# ESP_SCH.net
KiCad netlist of a schematic drawn in Altium Designer
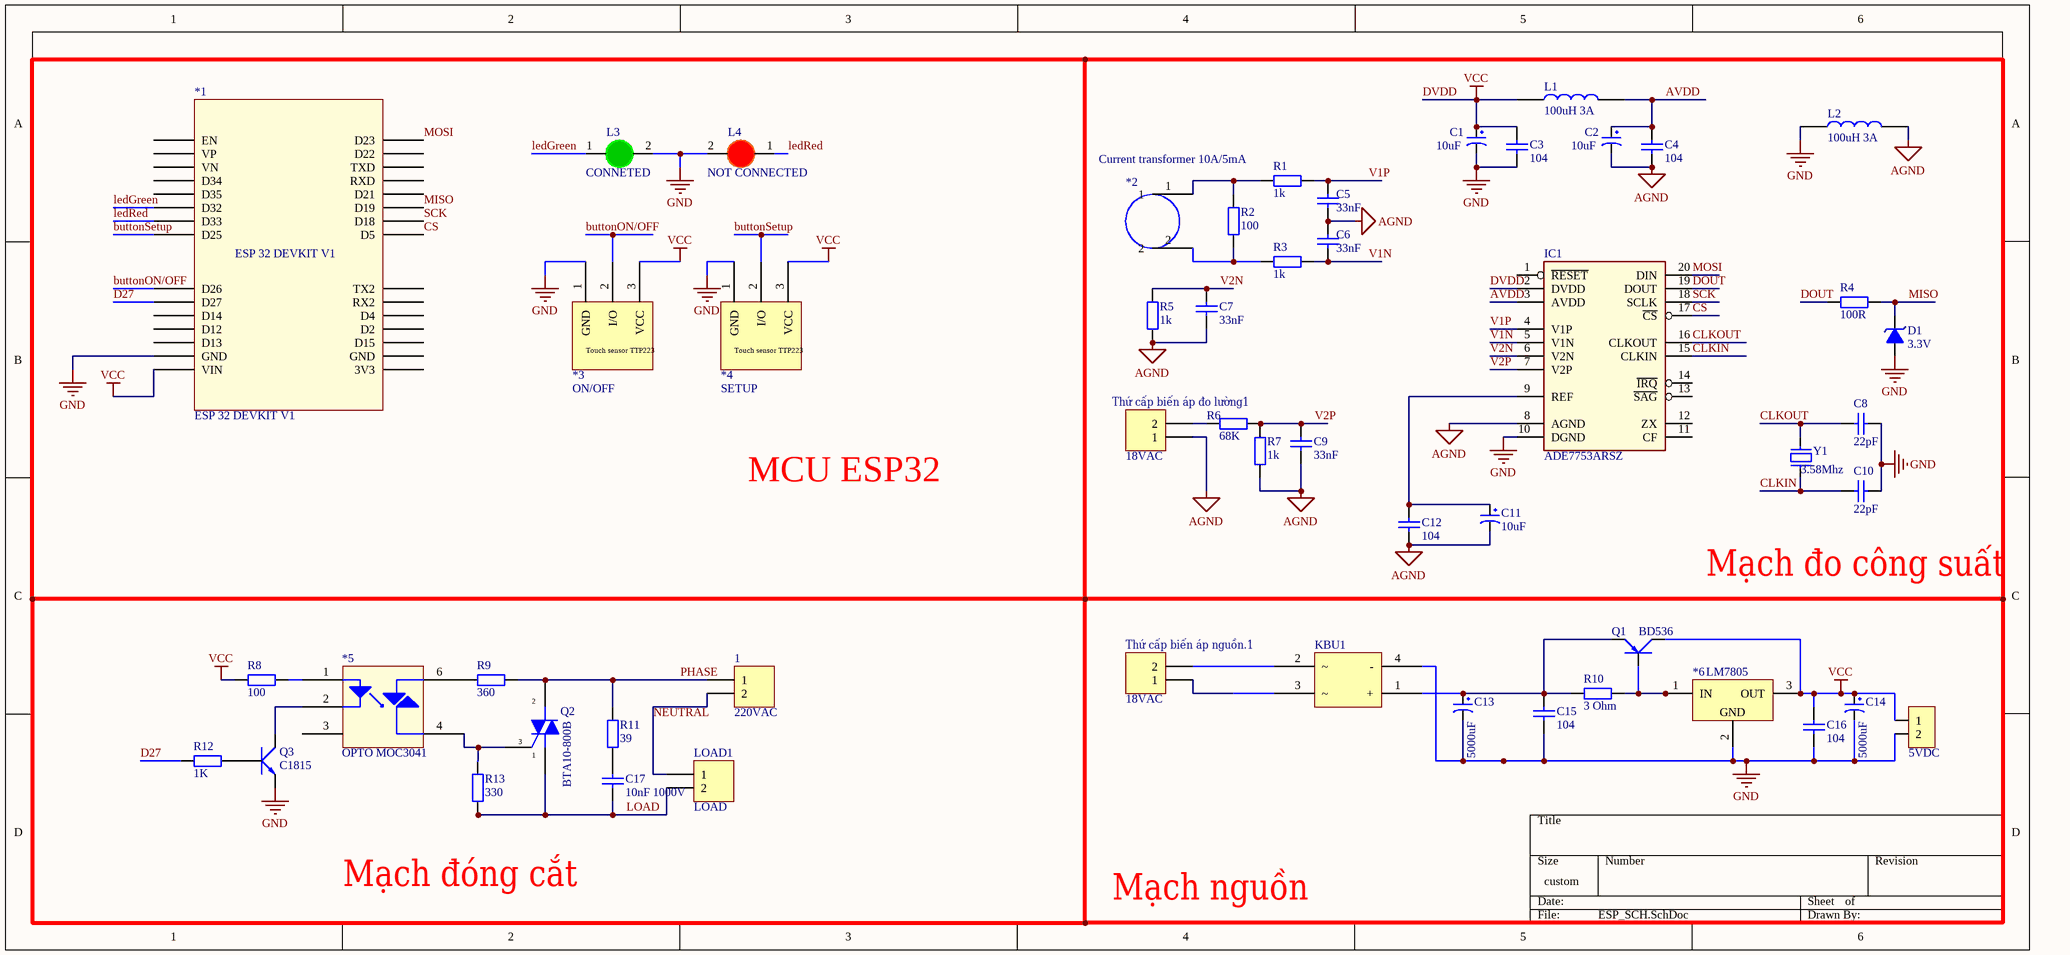
[diagram p0: ESP_SCH.SchDoc]

(export (version "E")
  (design (tool "Eeschema 10.0.6"))
  (components
    (comp (ref "*1")
      (value "ESP 32 DEVKIT V1")
      (footprint "ESP32 DEVKIT V1")
      (libsource (lib "TrungVan_Lib") (part "ESP 32 DEVKIT V1"))
    )
    (comp (ref "*2")
      (value "Current transformer 10A/5mA")
      (footprint "5A/5mA")
      (description "Current transformer 5A/5mA")
      (libsource (lib "TrungVan_Lib") (part "Current transformer"))
    )
    (comp (ref "*3")
      (value "ON/OFF")
      (footprint "TTP223")
      (libsource (lib "TrungVan_Lib") (part "Touch sensor"))
    )
    (comp (ref "*4")
      (value "SETUP")
      (footprint "TTP223")
      (libsource (lib "TrungVan_Lib") (part "Touch sensor"))
    )
    (comp (ref "*5")
      (value "OPTO MOC3041")
      (footprint "MOC3021")
      (libsource (lib "TrungVan_Lib") (part "OPTO MOC3021"))
    )
    (comp (ref "*6") (value "LM7805") (footprint "TO220") (libsource (lib "TrungVan_Lib") (part "LM780x")))
    (comp (ref "1")
      (value "220VAC")
      (footprint "KF127_2P")
      (description "Header, 2-Pin, pitch 5.08mm")
      (fields (field (name "MPN") "KF127-2P"))
      (libsource (lib "BYTECH_HW_LIB_2019 (1)") (part "KF127 2P"))
    )
    (comp (ref "C1")
      (value "10uF")
      (footprint "tu hoa 4mm")
      (description "Cắm")
      (libsource (lib "TrungVan_Lib") (part "Tu Hoa 10uF 25V 4x7"))
    )
    (comp (ref "C2")
      (value "10uF")
      (footprint "tu hoa 4mm")
      (description "Cắm")
      (libsource (lib "TrungVan_Lib") (part "Tu Hoa 10uF 25V 4x7"))
    )
    (comp (ref "C3")
      (value "104")
      (footprint "tu gom")
      (description "Cắm")
      (libsource (lib "TrungVan_Lib") (part "Tu gom 104 50V"))
    )
    (comp (ref "C4")
      (value "104")
      (footprint "tu gom")
      (description "Cắm")
      (libsource (lib "TrungVan_Lib") (part "Tu gom 104 50V"))
    )
    (comp (ref "C5")
      (value "33nF")
      (footprint "tu gom")
      (description "Cắm")
      (libsource (lib "TrungVan_Lib") (part "Tu gom 333 50V"))
    )
    (comp (ref "C6")
      (value "33nF")
      (footprint "tu gom")
      (description "Cắm")
      (libsource (lib "TrungVan_Lib") (part "Tu gom 333 50V"))
    )
    (comp (ref "C7")
      (value "33nF")
      (footprint "tu gom")
      (description "Cắm")
      (libsource (lib "TrungVan_Lib") (part "Tu gom 333 50V"))
    )
    (comp (ref "C8")
      (value "22pF")
      (footprint "tu gom")
      (description "Cắm")
      (libsource (lib "TrungVan_Lib") (part "Tu gom 221 50V"))
    )
    (comp (ref "C9")
      (value "33nF")
      (footprint "tu gom")
      (description "Cắm")
      (libsource (lib "TrungVan_Lib") (part "Tu gom 333 50V"))
    )
    (comp (ref "C10")
      (value "22pF")
      (footprint "tu gom")
      (description "Cắm")
      (libsource (lib "TrungVan_Lib") (part "Tu gom 221 50V"))
    )
    (comp (ref "C11")
      (value "10uF")
      (footprint "tu hoa 4mm")
      (description "Cắm")
      (libsource (lib "TrungVan_Lib") (part "Tu Hoa 10uF 25V 4x7"))
    )
    (comp (ref "C12")
      (value "104")
      (footprint "tu gom")
      (description "Cắm")
      (libsource (lib "TrungVan_Lib") (part "Tu gom 104 50V"))
    )
    (comp (ref "C13")
      (value "5000uF")
      (footprint "tu hoa 8mm")
      (description "Cắm")
      (libsource (lib "TrungVan_Lib") (part "Tu Hoa 1000uF 16V 8x20"))
    )
    (comp (ref "C14")
      (value "5000uF")
      (footprint "tu hoa 8mm")
      (description "Cắm")
      (libsource (lib "TrungVan_Lib") (part "Tu Hoa 1000uF 16V 8x20"))
    )
    (comp (ref "C15")
      (value "104")
      (footprint "tu gom")
      (description "Cắm")
      (libsource (lib "TrungVan_Lib") (part "Tu gom 473 50V"))
    )
    (comp (ref "C16")
      (value "104")
      (footprint "tu gom")
      (description "Cắm")
      (libsource (lib "TrungVan_Lib") (part "Tu gom 473 50V"))
    )
    (comp (ref "C17")
      (value "10nF 1000V")
      (footprint "tu tantalum dip5.08")
      (description "Cắm")
      (libsource (lib "TrungVan_Lib") (part "Tu tantalum 10nF DIP5.08"))
    )
    (comp (ref "D1")
      (value "3.3V")
      (footprint "DIODE 0.5A")
      (description "Dán")
      (libsource (lib "TrungVan_Lib") (part "Diode Zener 3.3V"))
    )
    (comp (ref "IC1")
      (value "ADE7753ARSZ")
      (footprint "ADE7753 dip")
      (description "Dán")
      (libsource (lib "TrungVan_Lib") (part "ADE7753 SMD SOP20"))
    )
    (comp (ref "JP1")
      (value "5VDC")
      (footprint "JP 1x2 DT")
      (description "Cắm")
      (libsource (lib "TrungVan_Lib") (part "JP 1x2 2.54 Duc Thang"))
    )
    (comp (ref "KBU1")
      (value "10A 1000V")
      (footprint "DIODE CAU 10A CAM")
      (description "Cắm")
      (libsource (lib "TrungVan_Lib") (part "Diode CAU 10A"))
    )
    (comp (ref "L1")
      (value "100uH 3A")
      (footprint "CUON_CAM 100UH")
      (description "Dán")
      (libsource (lib "TrungVan_Lib") (part "CUON CAM 100uH DIP"))
    )
    (comp (ref "L2")
      (value "100uH 3A")
      (footprint "CUON_CAM 100UH")
      (description "Dán")
      (libsource (lib "TrungVan_Lib") (part "CUON CAM 100uH DIP"))
    )
    (comp (ref "L3")
      (value "CONNETED")
      (footprint "LED-3MM-GREEN")
      (description "Cắm")
      (libsource (lib "TrungVan_Lib") (part "LED 3mm Xanh La"))
    )
    (comp (ref "L4")
      (value "NOT CONNECTED")
      (footprint "LED-3MM-RED")
      (description "Cắm")
      (libsource (lib "TrungVan_Lib") (part "LED 3mm Do"))
    )
    (comp (ref "LOAD1")
      (value "LOAD")
      (footprint "KF127_2P")
      (description "Header, 2-Pin, pitch 5.08mm")
      (fields (field (name "MPN") "KF127-2P"))
      (libsource (lib "BYTECH_HW_LIB_2019 (1)") (part "KF127 2P"))
    )
    (comp (ref "Q1")
      (value "BD536")
      (footprint "to220")
      (description "PNP 600mW, ECB")
      (libsource (lib "TrungVan_Lib") (part "A1015"))
    )
    (comp (ref "Q2")
      (value "BTA10-800B")
      (footprint "to220")
      (description "TRIAC 600V 40A TOP3")
      (fields
        (field (name "MANUFACTURER") "STMicroelectronics")
        (field (name "MANUFACTURER PART NUMBER") "BTA41-600BRG")
      )
      (libsource (lib "BYTECH_HW_LIB_2019 (1)") (part "BTA41-600BRG"))
    )
    (comp (ref "Q3")
      (value "C1815")
      (footprint "TO92")
      (description "NPN transistor")
      (libsource (lib "TrungVan_Lib") (part "C1815"))
    )
    (comp (ref "R1")
      (value "1k")
      (footprint "Dien tro")
      (description "Cắm")
      (libsource (lib "TrungVan_Lib") (part "Resistor"))
    )
    (comp (ref "R2")
      (value "100")
      (footprint "Dien tro")
      (description "Cắm")
      (libsource (lib "TrungVan_Lib") (part "Resistor"))
    )
    (comp (ref "R3")
      (value "1k")
      (footprint "Dien tro")
      (description "Cắm")
      (libsource (lib "TrungVan_Lib") (part "Resistor"))
    )
    (comp (ref "R4")
      (value "100R")
      (footprint "Dien tro")
      (description "Cắm")
      (libsource (lib "TrungVan_Lib") (part "Resistor"))
    )
    (comp (ref "R5")
      (value "1k")
      (footprint "Dien tro")
      (description "Cắm")
      (libsource (lib "TrungVan_Lib") (part "Resistor"))
    )
    (comp (ref "R6")
      (value "68K")
      (footprint "Dien tro")
      (description "Cắm")
      (libsource (lib "TrungVan_Lib") (part "Resistor"))
    )
    (comp (ref "R7")
      (value "1k")
      (footprint "Dien tro")
      (description "Cắm")
      (libsource (lib "TrungVan_Lib") (part "Resistor"))
    )
    (comp (ref "R8")
      (value "100")
      (footprint "Dien tro")
      (description "Cắm")
      (libsource (lib "TrungVan_Lib") (part "Resistor"))
    )
    (comp (ref "R9")
      (value "360")
      (footprint "Dien tro")
      (description "Cắm")
      (libsource (lib "TrungVan_Lib") (part "Resistor"))
    )
    (comp (ref "R10")
      (value "3 Ohm")
      (footprint "Dien tro")
      (description "Cắm")
      (libsource (lib "TrungVan_Lib") (part "Resistor"))
    )
    (comp (ref "R11")
      (value "39")
      (footprint "Dien tro")
      (description "Cắm")
      (libsource (lib "TrungVan_Lib") (part "Resistor"))
    )
    (comp (ref "R12")
      (value "1K")
      (footprint "Dien tro")
      (description "Cắm")
      (libsource (lib "TrungVan_Lib") (part "Resistor"))
    )
    (comp (ref "R13")
      (value "330")
      (footprint "Dien tro")
      (description "Cắm")
      (libsource (lib "TrungVan_Lib") (part "Resistor"))
    )
    (comp (ref "Thứ cấp biến áp nguồn.1")
      (value "18VAC")
      (footprint "KF127_2P")
      (description "Header, 2-Pin, pitch 5.08mm")
      (fields (field (name "MPN") "KF127-2P"))
      (libsource (lib "") (part "KF127 2P_1"))
    )
    (comp (ref "Thứ cấp biến áp đo lường1")
      (value "18VAC")
      (footprint "KF127_2P")
      (description "Header, 2-Pin, pitch 5.08mm")
      (fields (field (name "MPN") "KF127-2P"))
      (libsource (lib "") (part "KF127 2P_1"))
    )
    (comp (ref "Y1")
      (value "3.58Mhz")
      (footprint "Thach Anh 2 chan cam")
      (description "Crystal For all Crystal 2pin.")
      (libsource (lib "TrungVan_Lib") (part "Thach Anh 2 chan Cam"))
    )
  )
  (nets
    (net (code "1") (name "/AVDD") (class "Default")
      (node (ref "C2") (pin "1") (pinfunction "1_1") (pintype "passive"))
      (node (ref "C4") (pin "1") (pinfunction "1_1") (pintype "passive"))
      (node (ref "IC1") (pin "3") (pinfunction "AVDD_3") (pintype "passive"))
      (node (ref "L1") (pin "2") (pinfunction "2_2") (pintype "passive"))
    )
    (net (code "2") (name "/CLKIN") (class "Default")
      (node (ref "C10") (pin "2") (pinfunction "2_2") (pintype "passive"))
      (node (ref "IC1") (pin "15") (pinfunction "CLKIN_15") (pintype "passive"))
      (node (ref "Y1") (pin "1") (pinfunction "1_1") (pintype "passive"))
    )
    (net (code "3") (name "/CLKOUT") (class "Default")
      (node (ref "C8") (pin "2") (pinfunction "2_2") (pintype "passive"))
      (node (ref "IC1") (pin "16") (pinfunction "CLKOUT_16") (pintype "passive"))
      (node (ref "Y1") (pin "2") (pinfunction "2_2") (pintype "passive"))
    )
    (net (code "4") (name "/CS") (class "Default")
      (node (ref "*1") (pin "23") (pinfunction "D5_23") (pintype "passive"))
      (node (ref "IC1") (pin "17") (pinfunction "~{CS}_17") (pintype "passive"))
    )
    (net (code "5") (name "/D27") (class "Default")
      (node (ref "*1") (pin "10") (pinfunction "D27_10") (pintype "passive"))
      (node (ref "R12") (pin "2") (pinfunction "2_2") (pintype "passive"))
    )
    (net (code "6") (name "/DOUT") (class "Default")
      (node (ref "IC1") (pin "19") (pinfunction "DOUT_19") (pintype "passive"))
      (node (ref "R4") (pin "2") (pinfunction "2_2") (pintype "passive"))
    )
    (net (code "7") (name "/LOAD") (class "Default")
      (node (ref "C17") (pin "2") (pinfunction "2_2") (pintype "passive"))
      (node (ref "LOAD1") (pin "2") (pinfunction "2_2") (pintype "passive"))
      (node (ref "Q2") (pin "1") (pinfunction "M1_1") (pintype "passive"))
      (node (ref "R13") (pin "1") (pinfunction "1_1") (pintype "passive"))
    )
    (net (code "8") (name "/MISO") (class "Default")
      (node (ref "*1") (pin "25") (pinfunction "D19_25") (pintype "passive"))
      (node (ref "D1") (pin "2") (pinfunction "K_2") (pintype "passive"))
      (node (ref "R4") (pin "1") (pinfunction "1_1") (pintype "passive"))
    )
    (net (code "9") (name "/MOSI") (class "Default")
      (node (ref "*1") (pin "30") (pinfunction "D23_30") (pintype "passive"))
      (node (ref "IC1") (pin "20") (pinfunction "DIN_20") (pintype "passive"))
    )
    (net (code "10") (name "/NEUTRAL") (class "Default")
      (node (ref "1") (pin "2") (pinfunction "2_2") (pintype "passive"))
      (node (ref "LOAD1") (pin "1") (pinfunction "1_1") (pintype "passive"))
    )
    (net (code "11") (name "/PHASE") (class "Default")
      (node (ref "1") (pin "1") (pinfunction "1_1") (pintype "passive"))
      (node (ref "Q2") (pin "2") (pinfunction "M2_2") (pintype "passive"))
      (node (ref "R11") (pin "2") (pinfunction "2_2") (pintype "passive"))
      (node (ref "R9") (pin "2") (pinfunction "2_2") (pintype "passive"))
    )
    (net (code "12") (name "/SCK") (class "Default")
      (node (ref "*1") (pin "24") (pinfunction "D18_24") (pintype "passive"))
      (node (ref "IC1") (pin "18") (pinfunction "SCLK_18") (pintype "passive"))
    )
    (net (code "13") (name "/V1N") (class "Default")
      (node (ref "C6") (pin "2") (pinfunction "2_2") (pintype "passive"))
      (node (ref "IC1") (pin "5") (pinfunction "V1N_5") (pintype "passive"))
      (node (ref "R3") (pin "1") (pinfunction "1_1") (pintype "passive"))
    )
    (net (code "14") (name "/V1P") (class "Default")
      (node (ref "C5") (pin "1") (pinfunction "1_1") (pintype "passive"))
      (node (ref "IC1") (pin "4") (pinfunction "V1P_4") (pintype "passive"))
      (node (ref "R1") (pin "1") (pinfunction "1_1") (pintype "passive"))
    )
    (net (code "15") (name "/V2N") (class "Default")
      (node (ref "C7") (pin "1") (pinfunction "1_1") (pintype "passive"))
      (node (ref "IC1") (pin "6") (pinfunction "V2N_6") (pintype "passive"))
      (node (ref "R5") (pin "2") (pinfunction "2_2") (pintype "passive"))
    )
    (net (code "16") (name "/V2P") (class "Default")
      (node (ref "C9") (pin "1") (pinfunction "1_1") (pintype "passive"))
      (node (ref "IC1") (pin "7") (pinfunction "V2P_7") (pintype "passive"))
      (node (ref "R6") (pin "1") (pinfunction "1_1") (pintype "passive"))
      (node (ref "R7") (pin "2") (pinfunction "2_2") (pintype "passive"))
    )
    (net (code "17") (name "/buttonON{slash}OFF") (class "Default")
      (node (ref "*1") (pin "9") (pinfunction "D26_9") (pintype "passive"))
      (node (ref "*3") (pin "2") (pinfunction "I/O_2") (pintype "passive"))
    )
    (net (code "18") (name "/buttonSetup") (class "Default")
      (node (ref "*1") (pin "8") (pinfunction "D25_8") (pintype "passive"))
      (node (ref "*4") (pin "2") (pinfunction "I/O_2") (pintype "passive"))
    )
    (net (code "19") (name "/ledGreen") (class "Default")
      (node (ref "*1") (pin "6") (pinfunction "D32_6") (pintype "passive"))
      (node (ref "L3") (pin "1") (pinfunction "A_1") (pintype "passive"))
    )
    (net (code "20") (name "/ledRed") (class "Default")
      (node (ref "*1") (pin "7") (pinfunction "D33_7") (pintype "passive"))
      (node (ref "L4") (pin "1") (pinfunction "A_1") (pintype "passive"))
    )
    (net (code "21") (name "AGND") (class "Default")
      (node (ref "C11") (pin "2") (pinfunction "2_2") (pintype "passive"))
      (node (ref "C12") (pin "2") (pinfunction "2_2") (pintype "passive"))
      (node (ref "C2") (pin "2") (pinfunction "2_2") (pintype "passive"))
      (node (ref "C4") (pin "2") (pinfunction "2_2") (pintype "passive"))
      (node (ref "C5") (pin "2") (pinfunction "2_2") (pintype "passive"))
      (node (ref "C6") (pin "1") (pinfunction "1_1") (pintype "passive"))
      (node (ref "C7") (pin "2") (pinfunction "2_2") (pintype "passive"))
      (node (ref "C9") (pin "2") (pinfunction "2_2") (pintype "passive"))
      (node (ref "IC1") (pin "8") (pinfunction "AGND_8") (pintype "passive"))
      (node (ref "L2") (pin "2") (pinfunction "2_2") (pintype "passive"))
      (node (ref "R5") (pin "1") (pinfunction "1_1") (pintype "passive"))
      (node (ref "R7") (pin "1") (pinfunction "1_1") (pintype "passive"))
      (node (ref "Thứ cấp biến áp đo lường1") (pin "1") (pinfunction "1_1") (pintype "passive"))
    )
    (net (code "22") (name "GND") (class "Default")
      (node (ref "*1") (pin "14") (pinfunction "GND_14") (pintype "passive"))
      (node (ref "*3") (pin "1") (pinfunction "GND_1") (pintype "passive"))
      (node (ref "*4") (pin "1") (pinfunction "GND_1") (pintype "passive"))
      (node (ref "*6") (pin "2") (pinfunction "GND_2") (pintype "power_in"))
      (node (ref "C1") (pin "2") (pinfunction "2_2") (pintype "passive"))
      (node (ref "C10") (pin "1") (pinfunction "1_1") (pintype "passive"))
      (node (ref "C13") (pin "2") (pinfunction "2_2") (pintype "passive"))
      (node (ref "C14") (pin "2") (pinfunction "2_2") (pintype "passive"))
      (node (ref "C15") (pin "2") (pinfunction "2_2") (pintype "passive"))
      (node (ref "C16") (pin "2") (pinfunction "2_2") (pintype "passive"))
      (node (ref "C3") (pin "2") (pinfunction "2_2") (pintype "passive"))
      (node (ref "C8") (pin "1") (pinfunction "1_1") (pintype "passive"))
      (node (ref "D1") (pin "1") (pinfunction "A_1") (pintype "passive"))
      (node (ref "IC1") (pin "10") (pinfunction "DGND_10") (pintype "passive"))
      (node (ref "JP1") (pin "2") (pinfunction "2_2") (pintype "passive"))
      (node (ref "KBU1") (pin "4") (pinfunction "-_4") (pintype "passive"))
      (node (ref "L2") (pin "1") (pinfunction "1_1") (pintype "passive"))
      (node (ref "L3") (pin "2") (pinfunction "K_2") (pintype "passive"))
      (node (ref "L4") (pin "2") (pinfunction "K_2") (pintype "passive"))
      (node (ref "Q3") (pin "1") (pinfunction "E_1") (pintype "passive"))
    )
    (net (code "23") (name "Net-(*2-Pad1)") (class "Default")
      (node (ref "*2") (pin "1") (pinfunction "1_1") (pintype "passive"))
      (node (ref "R1") (pin "2") (pinfunction "2_2") (pintype "passive"))
      (node (ref "R2") (pin "2") (pinfunction "2_2") (pintype "passive"))
    )
    (net (code "24") (name "Net-(*2-Pad2)") (class "Default")
      (node (ref "*2") (pin "2") (pinfunction "2_2") (pintype "passive"))
      (node (ref "R2") (pin "1") (pinfunction "1_1") (pintype "passive"))
      (node (ref "R3") (pin "2") (pinfunction "2_2") (pintype "passive"))
    )
    (net (code "25") (name "Net-(*5-0)") (class "Default")
      (node (ref "*5") (pin "6") (pinfunction "0_6") (pintype "passive"))
      (node (ref "R9") (pin "1") (pinfunction "1_1") (pintype "passive"))
    )
    (net (code "26") (name "Net-(*5-2)") (class "Default")
      (node (ref "*5") (pin "4") (pinfunction "2_4") (pintype "passive"))
      (node (ref "Q2") (pin "3") (pinfunction "G_3") (pintype "passive"))
      (node (ref "R13") (pin "2") (pinfunction "2_2") (pintype "passive"))
    )
    (net (code "27") (name "Net-(*5-3)") (class "Default")
      (node (ref "*5") (pin "1") (pinfunction "3_1") (pintype "passive"))
      (node (ref "R8") (pin "1") (pinfunction "1_1") (pintype "passive"))
    )
    (net (code "28") (name "Net-(*5-4)") (class "Default")
      (node (ref "*5") (pin "2") (pinfunction "4_2") (pintype "passive"))
      (node (ref "Q3") (pin "2") (pinfunction "C_2") (pintype "passive"))
    )
    (net (code "29") (name "Net-(*6-IN)") (class "Default")
      (node (ref "*6") (pin "1") (pinfunction "IN_1") (pintype "power_in"))
      (node (ref "Q1") (pin "3") (pinfunction "B_3") (pintype "passive"))
      (node (ref "R10") (pin "1") (pinfunction "1_1") (pintype "passive"))
    )
    (net (code "30") (name "Net-(C17-Pad1)") (class "Default")
      (node (ref "C17") (pin "1") (pinfunction "1_1") (pintype "passive"))
      (node (ref "R11") (pin "1") (pinfunction "1_1") (pintype "passive"))
    )
    (net (code "31") (name "Net-(IC1-REF)") (class "Default")
      (node (ref "C11") (pin "1") (pinfunction "1_1") (pintype "passive"))
      (node (ref "C12") (pin "1") (pinfunction "1_1") (pintype "passive"))
      (node (ref "IC1") (pin "9") (pinfunction "REF_9") (pintype "passive"))
    )
    (net (code "32") (name "Net-(KBU1-+)") (class "Default")
      (node (ref "C13") (pin "1") (pinfunction "1_1") (pintype "passive"))
      (node (ref "C15") (pin "1") (pinfunction "1_1") (pintype "passive"))
      (node (ref "KBU1") (pin "1") (pinfunction "+_1") (pintype "passive"))
      (node (ref "Q1") (pin "1") (pinfunction "E_1") (pintype "passive"))
      (node (ref "R10") (pin "2") (pinfunction "2_2") (pintype "passive"))
    )
    (net (code "33") (name "Net-(KBU1-~-Pad2)") (class "Default")
      (node (ref "KBU1") (pin "2") (pinfunction "~_2") (pintype "passive"))
      (node (ref "Thứ cấp biến áp nguồn.1") (pin "2") (pinfunction "2_2") (pintype "passive"))
    )
    (net (code "34") (name "Net-(KBU1-~-Pad3)") (class "Default")
      (node (ref "KBU1") (pin "3") (pinfunction "~_3") (pintype "passive"))
      (node (ref "Thứ cấp biến áp nguồn.1") (pin "1") (pinfunction "1_1") (pintype "passive"))
    )
    (net (code "35") (name "Net-(Q3-B)") (class "Default")
      (node (ref "Q3") (pin "3") (pinfunction "B_3") (pintype "passive"))
      (node (ref "R12") (pin "1") (pinfunction "1_1") (pintype "passive"))
    )
    (net (code "36") (name "Net-(R6-Pad2)") (class "Default")
      (node (ref "R6") (pin "2") (pinfunction "2_2") (pintype "passive"))
      (node (ref "Thứ cấp biến áp đo lường1") (pin "2") (pinfunction "2_2") (pintype "passive"))
    )
    (net (code "37") (name "VCC") (class "Default")
      (node (ref "*1") (pin "15") (pinfunction "VIN_15") (pintype "passive"))
      (node (ref "*3") (pin "3") (pinfunction "VCC_3") (pintype "passive"))
      (node (ref "*4") (pin "3") (pinfunction "VCC_3") (pintype "passive"))
      (node (ref "*6") (pin "3") (pinfunction "OUT_3") (pintype "power_in"))
      (node (ref "C1") (pin "1") (pinfunction "1_1") (pintype "passive"))
      (node (ref "C14") (pin "1") (pinfunction "1_1") (pintype "passive"))
      (node (ref "C16") (pin "1") (pinfunction "1_1") (pintype "passive"))
      (node (ref "C3") (pin "1") (pinfunction "1_1") (pintype "passive"))
      (node (ref "IC1") (pin "2") (pinfunction "DVDD_2") (pintype "passive"))
      (node (ref "JP1") (pin "1") (pinfunction "1_1") (pintype "passive"))
      (node (ref "L1") (pin "1") (pinfunction "1_1") (pintype "passive"))
      (node (ref "Q1") (pin "2") (pinfunction "C_2") (pintype "passive"))
      (node (ref "R8") (pin "2") (pinfunction "2_2") (pintype "passive"))
    )
    (net (code "38") (name "unconnected-(*1-3V3-Pad16)") (class "Default")
      (node (ref "*1") (pin "16") (pinfunction "3V3_16") (pintype "passive"))
    )
    (net (code "39") (name "unconnected-(*1-D2-Pad19)") (class "Default")
      (node (ref "*1") (pin "19") (pinfunction "D2_19") (pintype "passive"))
    )
    (net (code "40") (name "unconnected-(*1-D4-Pad20)") (class "Default")
      (node (ref "*1") (pin "20") (pinfunction "D4_20") (pintype "passive"))
    )
    (net (code "41") (name "unconnected-(*1-D12-Pad12)") (class "Default")
      (node (ref "*1") (pin "12") (pinfunction "D12_12") (pintype "passive"))
    )
    (net (code "42") (name "unconnected-(*1-D13-Pad13)") (class "Default")
      (node (ref "*1") (pin "13") (pinfunction "D13_13") (pintype "passive"))
    )
    (net (code "43") (name "unconnected-(*1-D14-Pad11)") (class "Default")
      (node (ref "*1") (pin "11") (pinfunction "D14_11") (pintype "passive"))
    )
    (net (code "44") (name "unconnected-(*1-D15-Pad18)") (class "Default")
      (node (ref "*1") (pin "18") (pinfunction "D15_18") (pintype "passive"))
    )
    (net (code "45") (name "unconnected-(*1-D21-Pad26)") (class "Default")
      (node (ref "*1") (pin "26") (pinfunction "D21_26") (pintype "passive"))
    )
    (net (code "46") (name "unconnected-(*1-D22-Pad29)") (class "Default")
      (node (ref "*1") (pin "29") (pinfunction "D22_29") (pintype "passive"))
    )
    (net (code "47") (name "unconnected-(*1-D34-Pad4)") (class "Default")
      (node (ref "*1") (pin "4") (pinfunction "D34_4") (pintype "passive"))
    )
    (net (code "48") (name "unconnected-(*1-D35-Pad5)") (class "Default")
      (node (ref "*1") (pin "5") (pinfunction "D35_5") (pintype "passive"))
    )
    (net (code "49") (name "unconnected-(*1-EN-Pad1)") (class "Default")
      (node (ref "*1") (pin "1") (pinfunction "EN_1") (pintype "passive"))
    )
    (net (code "50") (name "unconnected-(*1-GND-Pad17)") (class "Default")
      (node (ref "*1") (pin "17") (pinfunction "GND_17") (pintype "passive"))
    )
    (net (code "51") (name "unconnected-(*1-RX2-Pad21)") (class "Default")
      (node (ref "*1") (pin "21") (pinfunction "RX2_21") (pintype "passive"))
    )
    (net (code "52") (name "unconnected-(*1-RXD-Pad27)") (class "Default")
      (node (ref "*1") (pin "27") (pinfunction "RXD_27") (pintype "passive"))
    )
    (net (code "53") (name "unconnected-(*1-TX2-Pad22)") (class "Default")
      (node (ref "*1") (pin "22") (pinfunction "TX2_22") (pintype "passive"))
    )
    (net (code "54") (name "unconnected-(*1-TXD-Pad28)") (class "Default")
      (node (ref "*1") (pin "28") (pinfunction "TXD_28") (pintype "passive"))
    )
    (net (code "55") (name "unconnected-(*1-VN-Pad3)") (class "Default")
      (node (ref "*1") (pin "3") (pinfunction "VN_3") (pintype "passive"))
    )
    (net (code "56") (name "unconnected-(*1-VP-Pad2)") (class "Default")
      (node (ref "*1") (pin "2") (pinfunction "VP_2") (pintype "passive"))
    )
    (net (code "57") (name "unconnected-(*5-5-Pad3)") (class "Default")
      (node (ref "*5") (pin "3") (pinfunction "5_3") (pintype "passive"))
    )
    (net (code "58") (name "unconnected-(*5-A-Pad1)") (class "Default")
      (node (ref "*5") (pin "1") (pinfunction "A_1") (pintype "passive"))
    )
    (net (code "59") (name "unconnected-(IC1-CF-Pad11)") (class "Default")
      (node (ref "IC1") (pin "11") (pinfunction "CF_11") (pintype "passive"))
    )
    (net (code "60") (name "unconnected-(IC1-ZX-Pad12)") (class "Default")
      (node (ref "IC1") (pin "12") (pinfunction "ZX_12") (pintype "passive"))
    )
    (net (code "61") (name "unconnected-(IC1-~{IRQ}-Pad14)") (class "Default")
      (node (ref "IC1") (pin "14") (pinfunction "~{IRQ}_14") (pintype "passive"))
    )
    (net (code "62") (name "unconnected-(IC1-~{RESET}-Pad1)") (class "Default")
      (node (ref "IC1") (pin "1") (pinfunction "~{RESET}_1") (pintype "passive"))
    )
    (net (code "63") (name "unconnected-(IC1-~{SAG}-Pad13)") (class "Default")
      (node (ref "IC1") (pin "13") (pinfunction "~{SAG}_13") (pintype "passive"))
    )
  )
)
